# home_auto.net
KiCad netlist of a schematic drawn in Altium Designer
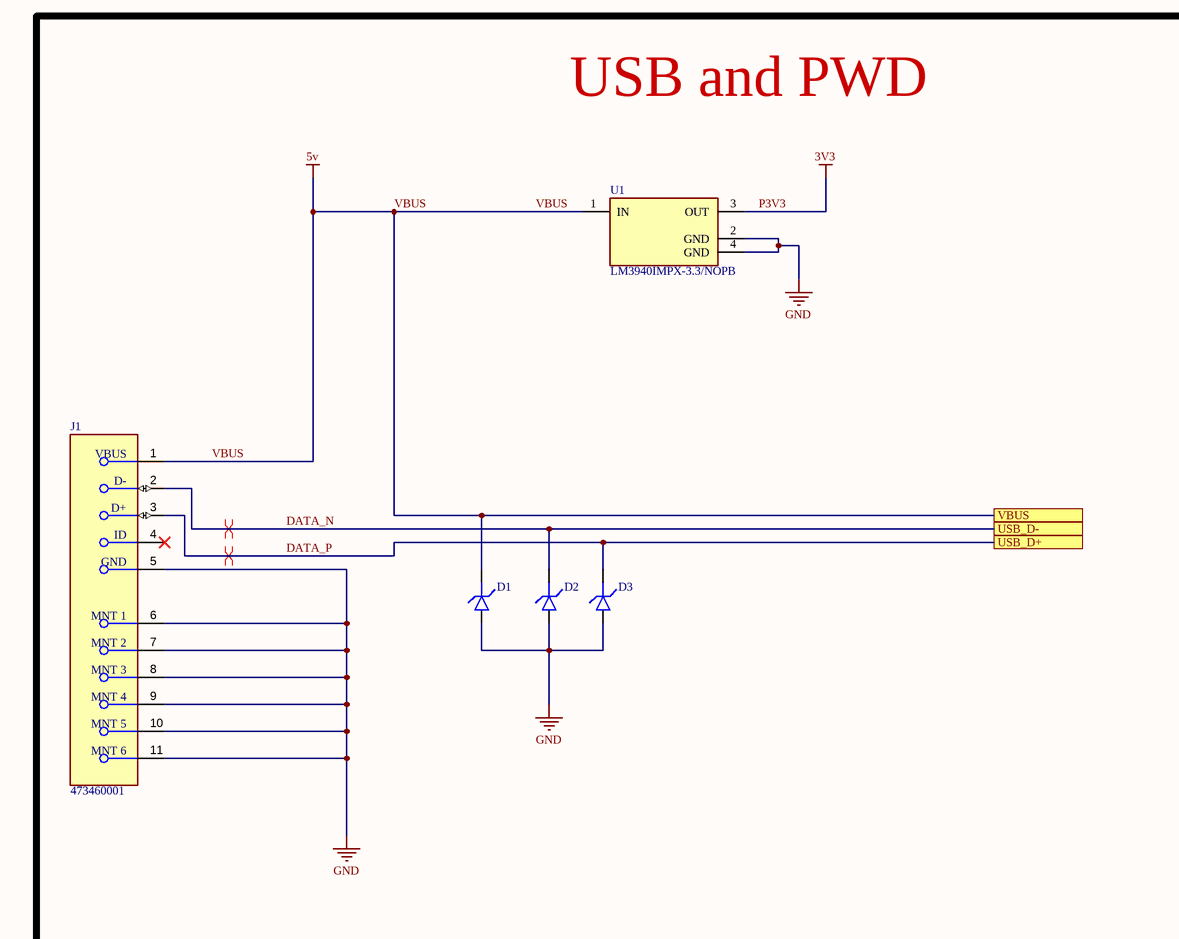
[diagram p0: home_auto.SchDoc, top left]
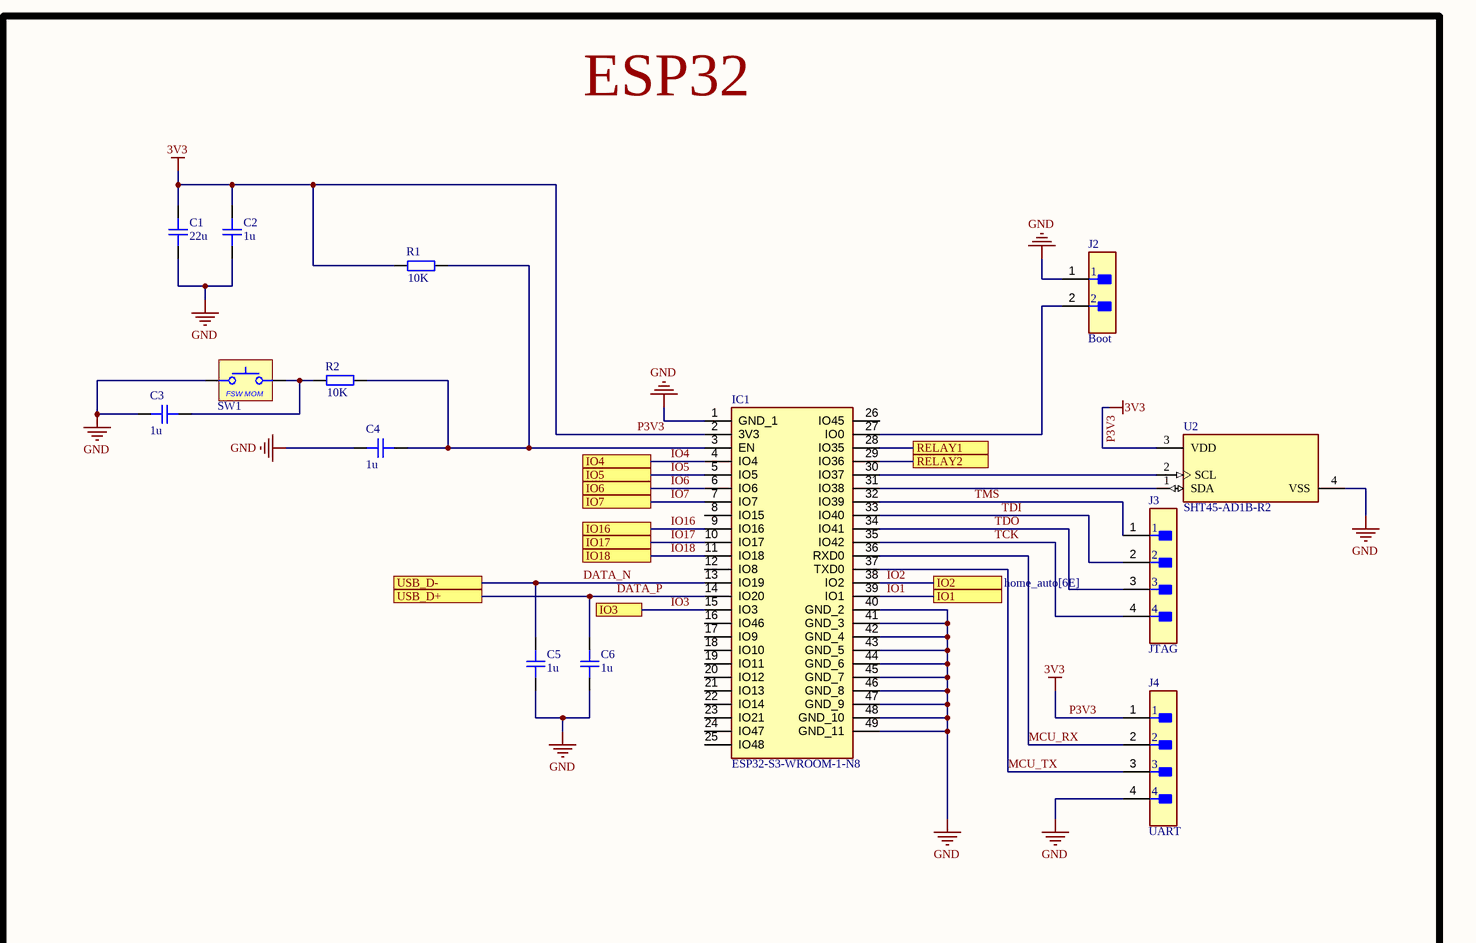
[diagram p1: home_auto.SchDoc, top right]
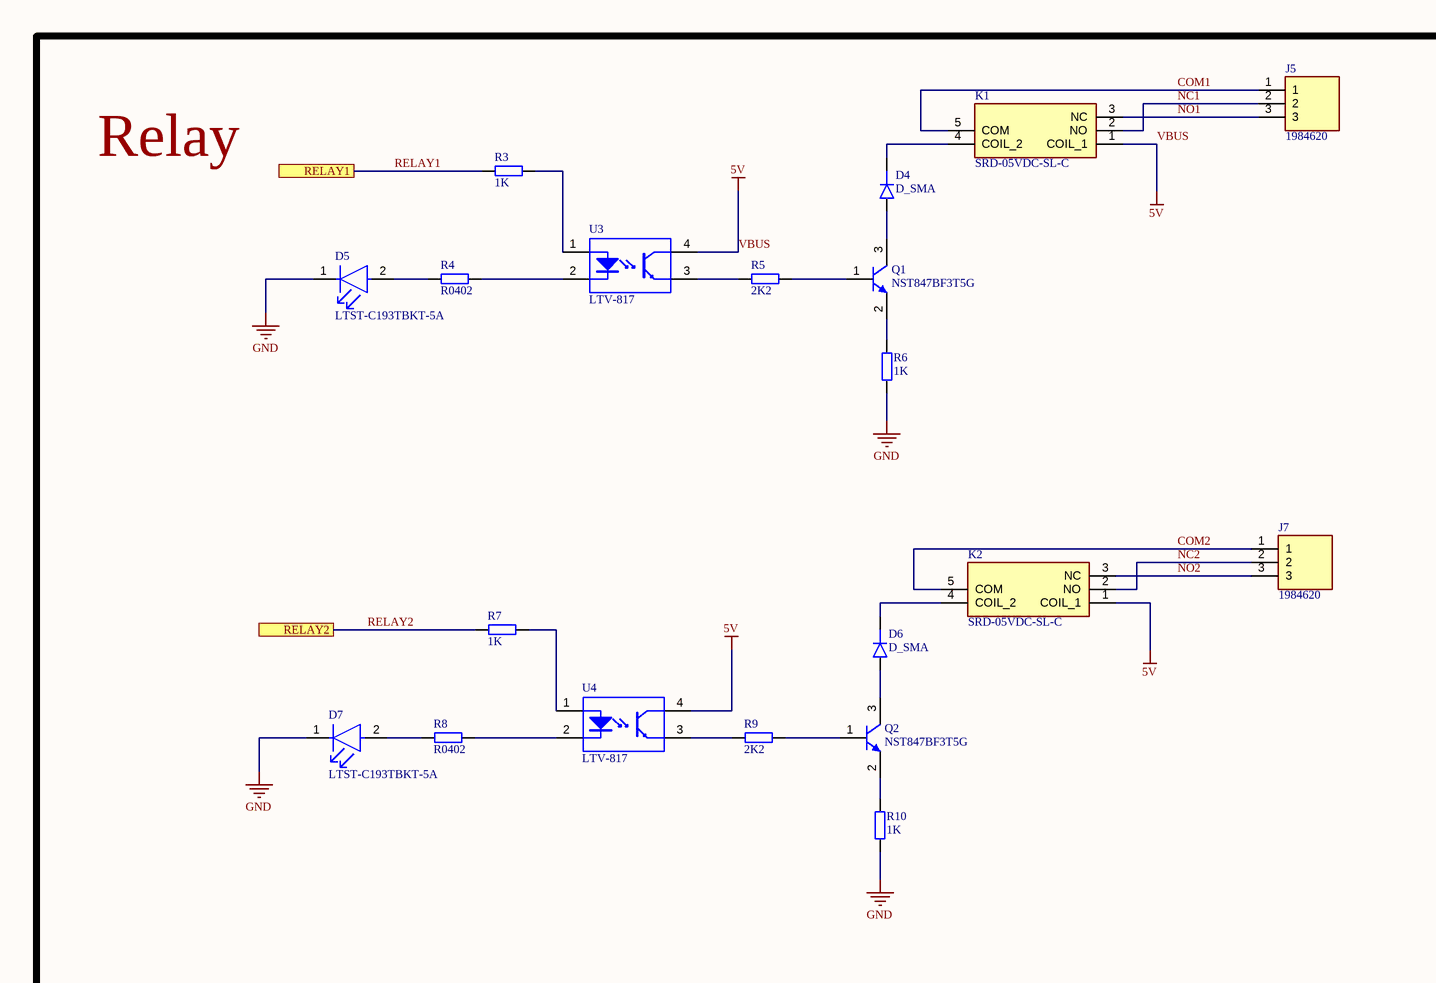
[diagram p2: home_auto.SchDoc, bottom left]
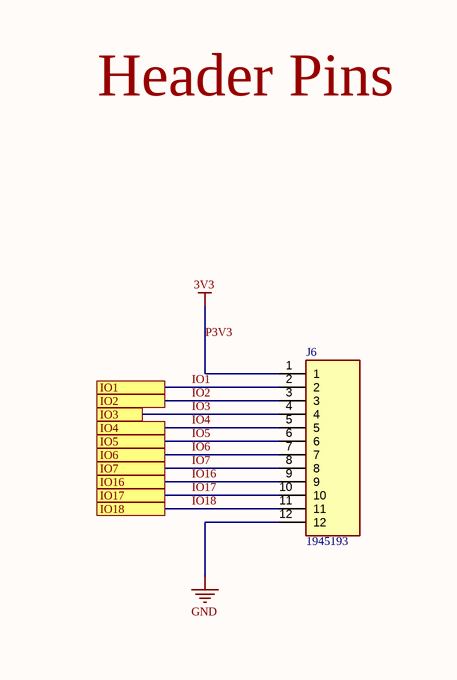
[diagram p3: home_auto.SchDoc, bottom right]

(export (version "E")
  (design (tool "Eeschema 10.0.6"))
  (components
    (comp (ref "C1")
      (value "22u")
      (footprint "CAP_0402")
      (description "Capacitor SMD 0402")
      (libsource (lib "Schematic-Lib-PhilsLab") (part "CAP_0402"))
    )
    (comp (ref "C2")
      (value "1u")
      (footprint "CAP_0402")
      (description "Capacitor SMD 0402")
      (libsource (lib "Schematic-Lib-PhilsLab") (part "CAP_0402"))
    )
    (comp (ref "C3")
      (value "1u")
      (footprint "CAP_0402")
      (description "Capacitor SMD 0402")
      (libsource (lib "Schematic-Lib-PhilsLab") (part "CAP_0402"))
    )
    (comp (ref "C4")
      (value "1u")
      (footprint "CAP_0402")
      (description "Capacitor SMD 0402")
      (libsource (lib "Schematic-Lib-PhilsLab") (part "CAP_0402"))
    )
    (comp (ref "C5")
      (value "1u")
      (footprint "CAP_0402")
      (description "Capacitor SMD 0402")
      (libsource (lib "Schematic-Lib-PhilsLab") (part "CAP_0402"))
    )
    (comp (ref "C6")
      (value "1u")
      (footprint "CAP_0402")
      (description "Capacitor SMD 0402")
      (libsource (lib "Schematic-Lib-PhilsLab") (part "CAP_0402"))
    )
    (comp (ref "D1")
      (value "~")
      (footprint "D_0402")
      (description "Diode TVS / ESD 0402")
      (libsource (lib "Schematic-Lib-PhilsLab") (part "D_TVS_0402"))
    )
    (comp (ref "D2")
      (value "~")
      (footprint "D_0402")
      (description "Diode TVS / ESD 0402")
      (libsource (lib "Schematic-Lib-PhilsLab") (part "D_TVS_0402"))
    )
    (comp (ref "D3")
      (value "~")
      (footprint "D_0402")
      (description "Diode TVS / ESD 0402")
      (libsource (lib "Schematic-Lib-PhilsLab") (part "D_TVS_0402"))
    )
    (comp (ref "D4")
      (value "D_SMA")
      (footprint "DO-214AC-2 (SMA)")
      (description "Diode SMD SMA (DO-214AA)")
      (libsource (lib "Schematic-Lib-PhilsLab") (part "D_SMA"))
    )
    (comp (ref "D5")
      (value "LTST-C193TBKT-5A")
      (footprint "FP-LTST-C193TBKT-5A-MFG")
      (description "LED BLUE CLEAR CHIP SMD")
      (libsource (lib "Altium Content Vault") (part "8706943c75ba83719d021d2fdc84c58"))
    )
    (comp (ref "D6")
      (value "D_SMA")
      (footprint "DO-214AC-2 (SMA)")
      (description "Diode SMD SMA (DO-214AA)")
      (libsource (lib "Schematic-Lib-PhilsLab") (part "D_SMA"))
    )
    (comp (ref "D7")
      (value "LTST-C193TBKT-5A")
      (footprint "FP-LTST-C193TBKT-5A-MFG")
      (description "LED BLUE CLEAR CHIP SMD")
      (libsource (lib "Altium Content Vault") (part "8706943c75ba83719d021d2fdc84c58"))
    )
    (comp (ref "IC1")
      (value "ESP32-S3-WROOM-1-N8")
      (footprint "SamacSys:ESP32S3WROOM1N8R2")
      (description "Integrated Circuit")
      (fields (field (name "MOUSER PART NUMBER") "356-ESP32-S3WROOM1N8"))
      (libsource (lib "*") (part "ESP32-S3-WROOM-1-N8"))
    )
    (comp (ref "J1")
      (value "473460001")
      (footprint "FP-473460001-MFG")
      (description "USB - micro B USB 2.0 Receptacle Connector 5 Position Surface Mount, Right Angle")
      (fields (field (name "OCTOPART") "https://octopart.com/47346-0001-molex-7164928"))
      (libsource (lib "Altium Content Vault") (part "53ae1f1d9b557310b43ca686e5bb76a"))
    )
    (comp (ref "J2")
      (value "Boot")
      (footprint "FP-M20-9990246-MFG")
      (description "CONN HEADER VERT 2POS 2.54MM")
      (fields
        (field (name "OCTOPART") "https://octopart.com/m20-9990246-harwin-2590635")
        (field (name "MANUFACTURER") "Harwin")
      )
      (libsource (lib "Altium Content Vault") (part "3bc925449376181038e59eaffc5286c"))
    )
    (comp (ref "J3")
      (value "JTAG")
      (footprint "FP-TMM-104-06-L-S-SM-MFG")
      (description "2MM TERMINAL STRIP")
      (libsource (lib "Altium Content Vault") (part "299a8cea1bdcbc3624fe62c390fa72c"))
    )
    (comp (ref "J4")
      (value "UART")
      (footprint "FP-TMM-104-06-L-S-SM-MFG")
      (description "2MM TERMINAL STRIP")
      (libsource (lib "Altium Content Vault") (part "299a8cea1bdcbc3624fe62c390fa72c"))
    )
    (comp (ref "J5")
      (value "1984620")
      (footprint "SamacSys:1984620")
      (description "Connector")
      (fields (field (name "MOUSER PART NUMBER") "651-1984620"))
      (libsource (lib "*") (part "1984620"))
    )
    (comp (ref "J6")
      (value "1945193")
      (footprint "SamacSys:1945193")
      (description "Connector")
      (fields (field (name "MOUSER PART NUMBER") "651-1945193"))
      (libsource (lib "*") (part "1945193"))
    )
    (comp (ref "J7")
      (value "1984620")
      (footprint "SamacSys:1984620")
      (description "Connector")
      (fields (field (name "MOUSER PART NUMBER") "651-1984620"))
      (libsource (lib "*") (part "1984620"))
    )
    (comp (ref "K1")
      (value "SRD-05VDC-SL-C")
      (footprint "SamacSys:SRD05VDCSLC")
      (description "Relay or Contactor")
      (libsource (lib "*") (part "SRD-05VDC-SL-C"))
    )
    (comp (ref "K2")
      (value "SRD-05VDC-SL-C")
      (footprint "SamacSys:SRD05VDCSLC")
      (description "Relay or Contactor")
      (libsource (lib "*") (part "SRD-05VDC-SL-C"))
    )
    (comp (ref "Q1")
      (value "NST847BF3T5G")
      (footprint "ONSC-SOT-1123-3-524AA_V")
      (description "NPN General Purpose Transistor, 3-Pin SOT-1123, Pb-Free, Tape and Reel")
      (fields (field (name "MANUFACTURER") "On Semiconductor"))
      (libsource (lib "Altium Content Vault") (part "ONSC-NPN-B1E2C3-3"))
    )
    (comp (ref "Q2")
      (value "NST847BF3T5G")
      (footprint "ONSC-SOT-1123-3-524AA_V")
      (description "NPN General Purpose Transistor, 3-Pin SOT-1123, Pb-Free, Tape and Reel")
      (fields (field (name "MANUFACTURER") "On Semiconductor"))
      (libsource (lib "Altium Content Vault") (part "ONSC-NPN-B1E2C3-3"))
    )
    (comp (ref "R1")
      (value "10K")
      (footprint "RES_0402")
      (description "Resistor SMD 0402")
      (libsource (lib "Schematic-Lib-PhilsLab") (part "RES_0402"))
    )
    (comp (ref "R2")
      (value "10K")
      (footprint "RES_0402")
      (description "Resistor SMD 0402")
      (libsource (lib "Schematic-Lib-PhilsLab") (part "RES_0402"))
    )
    (comp (ref "R3")
      (value "1K")
      (footprint "RES_0402")
      (description "Resistor SMD 0402")
      (libsource (lib "Schematic-Lib-PhilsLab") (part "RES_0402"))
    )
    (comp (ref "R4")
      (value "R0402")
      (footprint "RES_0402")
      (description "Resistor SMD 0402")
      (libsource (lib "Schematic-Lib-PhilsLab") (part "RES_0402"))
    )
    (comp (ref "R5")
      (value "2K2")
      (footprint "RES_0402")
      (description "Resistor SMD 0402")
      (libsource (lib "Schematic-Lib-PhilsLab") (part "RES_0402"))
    )
    (comp (ref "R6")
      (value "1K")
      (footprint "RES_0402")
      (description "Resistor SMD 0402")
      (libsource (lib "Schematic-Lib-PhilsLab") (part "RES_0402"))
    )
    (comp (ref "R7")
      (value "1K")
      (footprint "RES_0402")
      (description "Resistor SMD 0402")
      (libsource (lib "Schematic-Lib-PhilsLab") (part "RES_0402"))
    )
    (comp (ref "R8")
      (value "R0402")
      (footprint "RES_0402")
      (description "Resistor SMD 0402")
      (libsource (lib "Schematic-Lib-PhilsLab") (part "RES_0402"))
    )
    (comp (ref "R9")
      (value "2K2")
      (footprint "RES_0402")
      (description "Resistor SMD 0402")
      (libsource (lib "Schematic-Lib-PhilsLab") (part "RES_0402"))
    )
    (comp (ref "R10")
      (value "1K")
      (footprint "RES_0402")
      (description "Resistor SMD 0402")
      (libsource (lib "Schematic-Lib-PhilsLab") (part "RES_0402"))
    )
    (comp (ref "SW1")
      (value "FOOTSWITCH_MOM")
      (footprint "FOOTSWITCH_MOM")
      (description "Header 2.54mm THT for Momentary SPST Footswitch")
      (libsource (lib "Schematic-Lib-PhilsLab") (part "FOOTSWITCH_MOM"))
    )
    (comp (ref "U1")
      (value "LM3940IMPX-3.3/NOPB")
      (footprint "FP-DCY0004A-MFG")
      (description "IC REG LINEAR 3.3V 1A SOT223-4")
      (libsource (lib "Altium Content Vault") (part "c31ed432f589313beb2aec2175fc138"))
    )
    (comp (ref "U2")
      (value "SHT45-AD1B-R2")
      (footprint "FP-SHT45-AD1B-R2-MFG")
      (description "SENSOR HUMID/TEMP HIGH ACCURACY")
      (libsource (lib "Altium Content Vault") (part "c94db72837bc77e1548fc45e30bc2b4"))
    )
    (comp (ref "U3")
      (value "LTV-817")
      (footprint "LTST-LTV-817-4")
      (fields (field (name "MANUFACTURER") "Lite-On"))
      (libsource (lib "Altium Content Vault") (part "OPTO-AKEC-4"))
    )
    (comp (ref "U4")
      (value "LTV-817")
      (footprint "LTST-LTV-817-4")
      (fields (field (name "MANUFACTURER") "Lite-On"))
      (libsource (lib "Altium Content Vault") (part "OPTO-AKEC-4"))
    )
  )
  (nets
    (net (code "1") (name "/COM1") (class "Default")
      (node (ref "J5") (pin "1") (pinfunction "1_1") (pintype "passive"))
      (node (ref "K1") (pin "5") (pinfunction "COM_5") (pintype "passive"))
    )
    (net (code "2") (name "/COM2") (class "Default")
      (node (ref "J7") (pin "1") (pinfunction "1_1") (pintype "passive"))
      (node (ref "K2") (pin "5") (pinfunction "COM_5") (pintype "passive"))
    )
    (net (code "3") (name "/DATA_N") (class "Default")
      (node (ref "C5") (pin "2") (pinfunction "2_2") (pintype "passive"))
      (node (ref "D2") (pin "K") (pinfunction "K_K") (pintype "passive"))
      (node (ref "IC1") (pin "13") (pinfunction "IO19_13") (pintype "passive"))
      (node (ref "J1") (pin "2") (pinfunction "D-_2") (pintype "bidirectional"))
    )
    (net (code "4") (name "/DATA_P") (class "Default")
      (node (ref "C6") (pin "2") (pinfunction "2_2") (pintype "passive"))
      (node (ref "D3") (pin "K") (pinfunction "K_K") (pintype "passive"))
      (node (ref "IC1") (pin "14") (pinfunction "IO20_14") (pintype "passive"))
      (node (ref "J1") (pin "3") (pinfunction "D+_3") (pintype "bidirectional"))
    )
    (net (code "5") (name "/IO1") (class "Default")
      (node (ref "IC1") (pin "39") (pinfunction "IO1_39") (pintype "passive"))
      (node (ref "J6") (pin "2") (pinfunction "2_2") (pintype "passive"))
    )
    (net (code "6") (name "/IO2") (class "Default")
      (node (ref "IC1") (pin "38") (pinfunction "IO2_38") (pintype "passive"))
      (node (ref "J6") (pin "3") (pinfunction "3_3") (pintype "passive"))
    )
    (net (code "7") (name "/IO3") (class "Default")
      (node (ref "IC1") (pin "15") (pinfunction "IO3_15") (pintype "passive"))
      (node (ref "J6") (pin "4") (pinfunction "4_4") (pintype "passive"))
    )
    (net (code "8") (name "/IO4") (class "Default")
      (node (ref "IC1") (pin "4") (pinfunction "IO4_4") (pintype "passive"))
      (node (ref "J6") (pin "5") (pinfunction "5_5") (pintype "passive"))
    )
    (net (code "9") (name "/IO5") (class "Default")
      (node (ref "IC1") (pin "5") (pinfunction "IO5_5") (pintype "passive"))
      (node (ref "J6") (pin "6") (pinfunction "6_6") (pintype "passive"))
    )
    (net (code "10") (name "/IO6") (class "Default")
      (node (ref "IC1") (pin "6") (pinfunction "IO6_6") (pintype "passive"))
      (node (ref "J6") (pin "7") (pinfunction "7_7") (pintype "passive"))
    )
    (net (code "11") (name "/IO7") (class "Default")
      (node (ref "IC1") (pin "7") (pinfunction "IO7_7") (pintype "passive"))
      (node (ref "J6") (pin "8") (pinfunction "8_8") (pintype "passive"))
    )
    (net (code "12") (name "/IO16") (class "Default")
      (node (ref "IC1") (pin "9") (pinfunction "IO16_9") (pintype "passive"))
      (node (ref "J6") (pin "9") (pinfunction "9_9") (pintype "passive"))
    )
    (net (code "13") (name "/IO17") (class "Default")
      (node (ref "IC1") (pin "10") (pinfunction "IO17_10") (pintype "passive"))
      (node (ref "J6") (pin "10") (pinfunction "10_10") (pintype "passive"))
    )
    (net (code "14") (name "/IO18") (class "Default")
      (node (ref "IC1") (pin "11") (pinfunction "IO18_11") (pintype "passive"))
      (node (ref "J6") (pin "11") (pinfunction "11_11") (pintype "passive"))
    )
    (net (code "15") (name "/MCU_RX") (class "Default")
      (node (ref "IC1") (pin "36") (pinfunction "RXD0_36") (pintype "passive"))
      (node (ref "J4") (pin "2") (pinfunction "2_2") (pintype "passive"))
    )
    (net (code "16") (name "/MCU_TX") (class "Default")
      (node (ref "IC1") (pin "37") (pinfunction "TXD0_37") (pintype "passive"))
      (node (ref "J4") (pin "3") (pinfunction "3_3") (pintype "passive"))
    )
    (net (code "17") (name "/NC1") (class "Default")
      (node (ref "J5") (pin "2") (pinfunction "2_2") (pintype "passive"))
      (node (ref "K1") (pin "2") (pinfunction "NO_2") (pintype "passive"))
    )
    (net (code "18") (name "/NC2") (class "Default")
      (node (ref "J7") (pin "2") (pinfunction "2_2") (pintype "passive"))
      (node (ref "K2") (pin "2") (pinfunction "NO_2") (pintype "passive"))
    )
    (net (code "19") (name "/NO1") (class "Default")
      (node (ref "J5") (pin "3") (pinfunction "3_3") (pintype "passive"))
      (node (ref "K1") (pin "3") (pinfunction "NC_3") (pintype "passive"))
    )
    (net (code "20") (name "/NO2") (class "Default")
      (node (ref "J7") (pin "3") (pinfunction "3_3") (pintype "passive"))
      (node (ref "K2") (pin "3") (pinfunction "NC_3") (pintype "passive"))
    )
    (net (code "21") (name "/RELAY1") (class "Default")
      (node (ref "IC1") (pin "28") (pinfunction "IO35_28") (pintype "passive"))
      (node (ref "R3") (pin "1") (pinfunction "1_1") (pintype "passive"))
    )
    (net (code "22") (name "/RELAY2") (class "Default")
      (node (ref "IC1") (pin "29") (pinfunction "IO36_29") (pintype "passive"))
      (node (ref "R7") (pin "1") (pinfunction "1_1") (pintype "passive"))
    )
    (net (code "23") (name "/TCK") (class "Default")
      (node (ref "IC1") (pin "35") (pinfunction "IO42_35") (pintype "passive"))
      (node (ref "J3") (pin "4") (pinfunction "4_4") (pintype "passive"))
    )
    (net (code "24") (name "/TDI") (class "Default")
      (node (ref "IC1") (pin "33") (pinfunction "IO40_33") (pintype "passive"))
      (node (ref "J3") (pin "2") (pinfunction "2_2") (pintype "passive"))
    )
    (net (code "25") (name "/TDO") (class "Default")
      (node (ref "IC1") (pin "34") (pinfunction "IO41_34") (pintype "passive"))
      (node (ref "J3") (pin "3") (pinfunction "3_3") (pintype "passive"))
    )
    (net (code "26") (name "/TMS") (class "Default")
      (node (ref "IC1") (pin "32") (pinfunction "IO39_32") (pintype "passive"))
      (node (ref "J3") (pin "1") (pinfunction "1_1") (pintype "passive"))
    )
    (net (code "27") (name "3V3") (class "Default")
      (node (ref "C1") (pin "2") (pinfunction "2_2") (pintype "passive"))
      (node (ref "C2") (pin "2") (pinfunction "2_2") (pintype "passive"))
      (node (ref "IC1") (pin "2") (pinfunction "3V3_2") (pintype "passive"))
      (node (ref "J4") (pin "1") (pinfunction "1_1") (pintype "passive"))
      (node (ref "J6") (pin "1") (pinfunction "1_1") (pintype "passive"))
      (node (ref "R1") (pin "1") (pinfunction "1_1") (pintype "passive"))
      (node (ref "U1") (pin "3") (pinfunction "OUT_3") (pintype "passive"))
      (node (ref "U2") (pin "3") (pinfunction "VDD_3") (pintype "power_in"))
    )
    (net (code "28") (name "5V") (class "Default")
      (node (ref "D1") (pin "K") (pinfunction "K_K") (pintype "passive"))
      (node (ref "J1") (pin "1") (pinfunction "VBUS_1") (pintype "power_in"))
      (node (ref "K1") (pin "1") (pinfunction "COIL_1_1") (pintype "passive"))
      (node (ref "K2") (pin "1") (pinfunction "COIL_1_1") (pintype "passive"))
      (node (ref "U1") (pin "1") (pinfunction "IN_1") (pintype "power_in"))
      (node (ref "U3") (pin "4") (pinfunction "COLLECTOR_4") (pintype "passive"))
      (node (ref "U4") (pin "4") (pinfunction "COLLECTOR_4") (pintype "passive"))
    )
    (net (code "29") (name "GND") (class "Default")
      (node (ref "C1") (pin "1") (pinfunction "1_1") (pintype "passive"))
      (node (ref "C2") (pin "1") (pinfunction "1_1") (pintype "passive"))
      (node (ref "C3") (pin "2") (pinfunction "2_2") (pintype "passive"))
      (node (ref "C4") (pin "2") (pinfunction "2_2") (pintype "passive"))
      (node (ref "C5") (pin "1") (pinfunction "1_1") (pintype "passive"))
      (node (ref "C6") (pin "1") (pinfunction "1_1") (pintype "passive"))
      (node (ref "D1") (pin "A") (pinfunction "A_A") (pintype "passive"))
      (node (ref "D2") (pin "A") (pinfunction "A_A") (pintype "passive"))
      (node (ref "D3") (pin "A") (pinfunction "A_A") (pintype "passive"))
      (node (ref "D5") (pin "1") (pinfunction "C_1") (pintype "passive"))
      (node (ref "D7") (pin "1") (pinfunction "C_1") (pintype "passive"))
      (node (ref "IC1") (pin "1") (pinfunction "GND_1_1") (pintype "passive"))
      (node (ref "IC1") (pin "40") (pinfunction "GND_2_40") (pintype "passive"))
      (node (ref "IC1") (pin "41") (pinfunction "GND_3_41") (pintype "passive"))
      (node (ref "IC1") (pin "42") (pinfunction "GND_4_42") (pintype "passive"))
      (node (ref "IC1") (pin "43") (pinfunction "GND_5_43") (pintype "passive"))
      (node (ref "IC1") (pin "44") (pinfunction "GND_6_44") (pintype "passive"))
      (node (ref "IC1") (pin "45") (pinfunction "GND_7_45") (pintype "passive"))
      (node (ref "IC1") (pin "46") (pinfunction "GND_8_46") (pintype "passive"))
      (node (ref "IC1") (pin "47") (pinfunction "GND_9_47") (pintype "passive"))
      (node (ref "IC1") (pin "48") (pinfunction "GND_10_48") (pintype "passive"))
      (node (ref "IC1") (pin "49") (pinfunction "GND_11_49") (pintype "passive"))
      (node (ref "J1") (pin "10") (pinfunction "MNT_5_10") (pintype "passive"))
      (node (ref "J1") (pin "11") (pinfunction "MNT_6_11") (pintype "passive"))
      (node (ref "J1") (pin "5") (pinfunction "GND_5") (pintype "power_in"))
      (node (ref "J1") (pin "6") (pinfunction "MNT_1_6") (pintype "passive"))
      (node (ref "J1") (pin "7") (pinfunction "MNT_2_7") (pintype "passive"))
      (node (ref "J1") (pin "8") (pinfunction "MNT_3_8") (pintype "passive"))
      (node (ref "J1") (pin "9") (pinfunction "MNT_4_9") (pintype "passive"))
      (node (ref "J2") (pin "1") (pinfunction "1_1") (pintype "passive"))
      (node (ref "J4") (pin "4") (pinfunction "4_4") (pintype "passive"))
      (node (ref "J6") (pin "12") (pinfunction "12_12") (pintype "passive"))
      (node (ref "R10") (pin "1") (pinfunction "1_1") (pintype "passive"))
      (node (ref "R6") (pin "1") (pinfunction "1_1") (pintype "passive"))
      (node (ref "SW1") (pin "1") (pintype "passive"))
      (node (ref "U1") (pin "2") (pinfunction "GND_2") (pintype "power_in"))
      (node (ref "U1") (pin "4") (pinfunction "GND_4") (pintype "power_in"))
      (node (ref "U2") (pin "4") (pinfunction "VSS_4") (pintype "power_in"))
    )
    (net (code "30") (name "Net-(C3-Pad1)") (class "Default")
      (node (ref "C3") (pin "1") (pinfunction "1_1") (pintype "passive"))
      (node (ref "R2") (pin "1") (pinfunction "1_1") (pintype "passive"))
      (node (ref "SW1") (pin "2") (pintype "passive"))
    )
    (net (code "31") (name "Net-(D5-A)") (class "Default")
      (node (ref "D5") (pin "2") (pinfunction "A_2") (pintype "passive"))
      (node (ref "R4") (pin "1") (pinfunction "1_1") (pintype "passive"))
    )
    (net (code "32") (name "Net-(D7-A)") (class "Default")
      (node (ref "D7") (pin "2") (pinfunction "A_2") (pintype "passive"))
      (node (ref "R8") (pin "1") (pinfunction "1_1") (pintype "passive"))
    )
    (net (code "33") (name "Net-(IC1-EN)") (class "Default")
      (node (ref "C4") (pin "1") (pinfunction "1_1") (pintype "passive"))
      (node (ref "IC1") (pin "3") (pinfunction "EN_3") (pintype "passive"))
      (node (ref "R1") (pin "2") (pinfunction "2_2") (pintype "passive"))
      (node (ref "R2") (pin "2") (pinfunction "2_2") (pintype "passive"))
    )
    (net (code "34") (name "Net-(IC1-IO0)") (class "Default")
      (node (ref "IC1") (pin "27") (pinfunction "IO0_27") (pintype "passive"))
      (node (ref "J2") (pin "2") (pinfunction "2_2") (pintype "passive"))
    )
    (net (code "35") (name "Net-(IC1-IO37)") (class "Default")
      (node (ref "IC1") (pin "30") (pinfunction "IO37_30") (pintype "passive"))
      (node (ref "U2") (pin "2") (pinfunction "SCL_2") (pintype "input"))
    )
    (net (code "36") (name "Net-(IC1-IO38)") (class "Default")
      (node (ref "IC1") (pin "31") (pinfunction "IO38_31") (pintype "passive"))
      (node (ref "U2") (pin "1") (pinfunction "SDA_1") (pintype "bidirectional"))
    )
    (net (code "37") (name "Net-(K1-COIL_2)") (class "Default")
      (node (ref "D4") (pin "K") (pinfunction "K_K") (pintype "passive"))
      (node (ref "K1") (pin "4") (pinfunction "COIL_2_4") (pintype "passive"))
    )
    (net (code "38") (name "Net-(K2-COIL_2)") (class "Default")
      (node (ref "D6") (pin "K") (pinfunction "K_K") (pintype "passive"))
      (node (ref "K2") (pin "4") (pinfunction "COIL_2_4") (pintype "passive"))
    )
    (net (code "39") (name "Net-(Q1-B)") (class "Default")
      (node (ref "Q1") (pin "1") (pinfunction "B_1") (pintype "passive"))
      (node (ref "R5") (pin "2") (pinfunction "2_2") (pintype "passive"))
    )
    (net (code "40") (name "Net-(Q1-C)") (class "Default")
      (node (ref "D4") (pin "A") (pinfunction "A_A") (pintype "passive"))
      (node (ref "Q1") (pin "3") (pinfunction "C_3") (pintype "passive"))
    )
    (net (code "41") (name "Net-(Q1-E)") (class "Default")
      (node (ref "Q1") (pin "2") (pinfunction "E_2") (pintype "passive"))
      (node (ref "R6") (pin "2") (pinfunction "2_2") (pintype "passive"))
    )
    (net (code "42") (name "Net-(Q2-B)") (class "Default")
      (node (ref "Q2") (pin "1") (pinfunction "B_1") (pintype "passive"))
      (node (ref "R9") (pin "2") (pinfunction "2_2") (pintype "passive"))
    )
    (net (code "43") (name "Net-(Q2-C)") (class "Default")
      (node (ref "D6") (pin "A") (pinfunction "A_A") (pintype "passive"))
      (node (ref "Q2") (pin "3") (pinfunction "C_3") (pintype "passive"))
    )
    (net (code "44") (name "Net-(Q2-E)") (class "Default")
      (node (ref "Q2") (pin "2") (pinfunction "E_2") (pintype "passive"))
      (node (ref "R10") (pin "2") (pinfunction "2_2") (pintype "passive"))
    )
    (net (code "45") (name "Net-(U3-ANODE)") (class "Default")
      (node (ref "R3") (pin "2") (pinfunction "2_2") (pintype "passive"))
      (node (ref "U3") (pin "1") (pinfunction "ANODE_1") (pintype "passive"))
    )
    (net (code "46") (name "Net-(U3-CATHODE)") (class "Default")
      (node (ref "R4") (pin "2") (pinfunction "2_2") (pintype "passive"))
      (node (ref "U3") (pin "2") (pinfunction "CATHODE_2") (pintype "passive"))
    )
    (net (code "47") (name "Net-(U3-EMITTER)") (class "Default")
      (node (ref "R5") (pin "1") (pinfunction "1_1") (pintype "passive"))
      (node (ref "U3") (pin "3") (pinfunction "EMITTER_3") (pintype "passive"))
    )
    (net (code "48") (name "Net-(U4-ANODE)") (class "Default")
      (node (ref "R7") (pin "2") (pinfunction "2_2") (pintype "passive"))
      (node (ref "U4") (pin "1") (pinfunction "ANODE_1") (pintype "passive"))
    )
    (net (code "49") (name "Net-(U4-CATHODE)") (class "Default")
      (node (ref "R8") (pin "2") (pinfunction "2_2") (pintype "passive"))
      (node (ref "U4") (pin "2") (pinfunction "CATHODE_2") (pintype "passive"))
    )
    (net (code "50") (name "Net-(U4-EMITTER)") (class "Default")
      (node (ref "R9") (pin "1") (pinfunction "1_1") (pintype "passive"))
      (node (ref "U4") (pin "3") (pinfunction "EMITTER_3") (pintype "passive"))
    )
    (net (code "51") (name "unconnected-(IC1-IO8-Pad12)") (class "Default")
      (node (ref "IC1") (pin "12") (pinfunction "IO8_12") (pintype "passive"))
    )
    (net (code "52") (name "unconnected-(IC1-IO9-Pad17)") (class "Default")
      (node (ref "IC1") (pin "17") (pinfunction "IO9_17") (pintype "passive"))
    )
    (net (code "53") (name "unconnected-(IC1-IO10-Pad18)") (class "Default")
      (node (ref "IC1") (pin "18") (pinfunction "IO10_18") (pintype "passive"))
    )
    (net (code "54") (name "unconnected-(IC1-IO11-Pad19)") (class "Default")
      (node (ref "IC1") (pin "19") (pinfunction "IO11_19") (pintype "passive"))
    )
    (net (code "55") (name "unconnected-(IC1-IO12-Pad20)") (class "Default")
      (node (ref "IC1") (pin "20") (pinfunction "IO12_20") (pintype "passive"))
    )
    (net (code "56") (name "unconnected-(IC1-IO13-Pad21)") (class "Default")
      (node (ref "IC1") (pin "21") (pinfunction "IO13_21") (pintype "passive"))
    )
    (net (code "57") (name "unconnected-(IC1-IO14-Pad22)") (class "Default")
      (node (ref "IC1") (pin "22") (pinfunction "IO14_22") (pintype "passive"))
    )
    (net (code "58") (name "unconnected-(IC1-IO15-Pad8)") (class "Default")
      (node (ref "IC1") (pin "8") (pinfunction "IO15_8") (pintype "passive"))
    )
    (net (code "59") (name "unconnected-(IC1-IO21-Pad23)") (class "Default")
      (node (ref "IC1") (pin "23") (pinfunction "IO21_23") (pintype "passive"))
    )
    (net (code "60") (name "unconnected-(IC1-IO45-Pad26)") (class "Default")
      (node (ref "IC1") (pin "26") (pinfunction "IO45_26") (pintype "passive"))
    )
    (net (code "61") (name "unconnected-(IC1-IO46-Pad16)") (class "Default")
      (node (ref "IC1") (pin "16") (pinfunction "IO46_16") (pintype "passive"))
    )
    (net (code "62") (name "unconnected-(IC1-IO47-Pad24)") (class "Default")
      (node (ref "IC1") (pin "24") (pinfunction "IO47_24") (pintype "passive"))
    )
    (net (code "63") (name "unconnected-(IC1-IO48-Pad25)") (class "Default")
      (node (ref "IC1") (pin "25") (pinfunction "IO48_25") (pintype "passive"))
    )
    (net (code "64") (name "unconnected-(J1-ID-Pad4)") (class "Default")
      (node (ref "J1") (pin "4") (pinfunction "ID_4") (pintype "passive+no_connect"))
    )
  )
)
